# Sheet2.net
KiCad netlist of a schematic drawn in Altium Designer
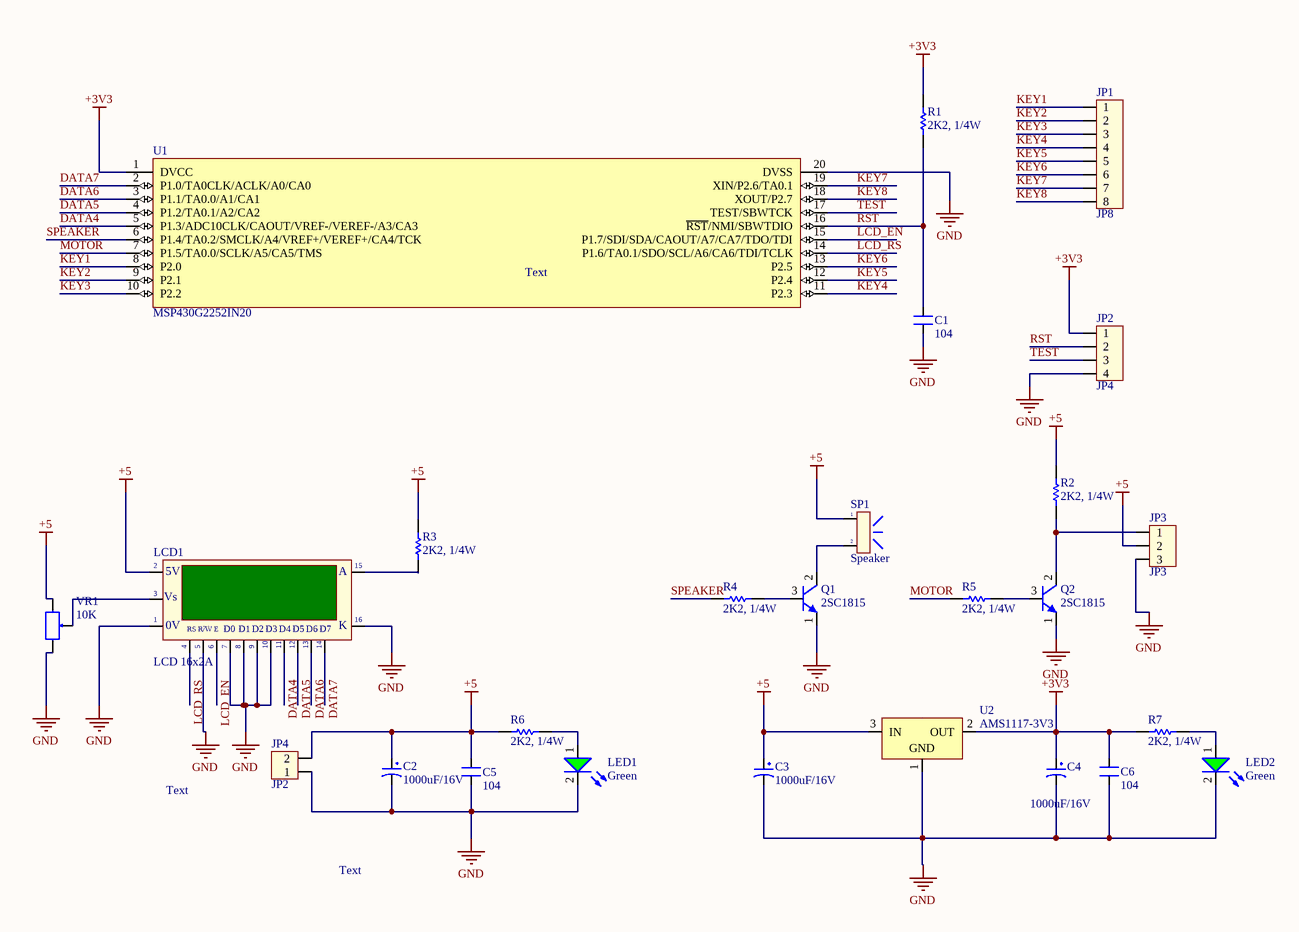
[diagram p0: Sheet2.SchDoc]

(export (version "E")
  (design (tool "Eeschema 10.0.6"))
  (components
    (comp (ref "C1")
      (value "104")
      (footprint "CN2")
      (description "Cap np 104 => 105pF")
      (libsource (lib "lpson") (part "CN2"))
    )
    (comp (ref "C2")
      (value "1000uF/16V")
      (footprint "CP1.5/3.4")
      (description "Cap 1000uF/16V - 220uF/50V")
      (libsource (lib "lpson") (part "CP4"))
    )
    (comp (ref "C3")
      (value "1000uF/16V")
      (footprint "CP1.5/3.4")
      (description "Cap 1000uF/16V - 220uF/50V")
      (libsource (lib "lpson") (part "CP4"))
    )
    (comp (ref "C4")
      (value "1000uF/16V")
      (footprint "CP1.5/3.4")
      (description "Cap 1000uF/16V - 220uF/50V")
      (libsource (lib "lpson") (part "CP4"))
    )
    (comp (ref "C5")
      (value "104")
      (footprint "CN2")
      (description "Cap np 104 => 105pF")
      (libsource (lib "lpson") (part "CN2"))
    )
    (comp (ref "C6")
      (value "104")
      (footprint "CN2")
      (description "Cap np 104 => 105pF")
      (libsource (lib "lpson") (part "CN2"))
    )
    (comp (ref "JP1")
      (value "JP8")
      (footprint "CON8")
      (description "Connector 8")
      (libsource (lib "lpson") (part "Con8"))
    )
    (comp (ref "JP2")
      (value "JP4")
      (footprint "CON4")
      (description "Connector 4")
      (libsource (lib "lpson") (part "Con4"))
    )
    (comp (ref "JP3")
      (value "JP3")
      (footprint "CON3")
      (description "Connector 3")
      (libsource (lib "lpson") (part "Con3"))
    )
    (comp (ref "JP4")
      (value "JP2")
      (footprint "CON2")
      (description "Connector 2")
      (libsource (lib "lpson") (part "Con2"))
    )
    (comp (ref "LCD1")
      (value "LCD 16x2A")
      (footprint "LCD16x2")
      (description "LCD dipslay 16 char, 2 line")
      (libsource (lib "lpson") (part "LCD16x2A"))
    )
    (comp (ref "LED1")
      (value "Green")
      (footprint "LED3G")
      (description "LED Green 3mm")
      (fields (field (name "Comment") "LED_G_3"))
      (libsource (lib "lpson") (part "LED_GREEN_3MM"))
    )
    (comp (ref "LED2")
      (value "Green")
      (footprint "LED3G")
      (description "LED Green 3mm")
      (fields (field (name "Comment") "LED_G_3"))
      (libsource (lib "lpson") (part "LED_GREEN_3MM"))
    )
    (comp (ref "Q1")
      (value "2SC1815")
      (footprint "2SC1815")
      (description "Trans NPN 50V 150mA TO-92")
      (libsource (lib "lpson") (part "2SC1815"))
    )
    (comp (ref "Q2")
      (value "2SC1815")
      (footprint "2SC1815")
      (description "Trans NPN 50V 150mA TO-92")
      (libsource (lib "lpson") (part "2SC1815"))
    )
    (comp (ref "R1")
      (value "2K2, 1/4W")
      (footprint "RES 1/4W CFR25")
      (description "RES CF AXIAL-0.3 5% 1/4W 2K2")
      (fields (field (name "Comment") "CF1/4W2K2J25"))
      (libsource (lib "lpson") (part "CF1/4W2K2J25"))
    )
    (comp (ref "R2")
      (value "2K2, 1/4W")
      (footprint "RES 1/4W CFR25")
      (description "RES CF AXIAL-0.3 5% 1/4W 2K2")
      (fields (field (name "Comment") "CF1/4W2K2J25"))
      (libsource (lib "lpson") (part "CF1/4W2K2J25"))
    )
    (comp (ref "R3")
      (value "2K2, 1/4W")
      (footprint "RES 1/4W CFR25")
      (description "RES CF AXIAL-0.3 5% 1/4W 2K2")
      (fields (field (name "Comment") "CF1/4W2K2J25"))
      (libsource (lib "lpson") (part "CF1/4W2K2J25"))
    )
    (comp (ref "R4")
      (value "2K2, 1/4W")
      (footprint "RES 1/4W CFR25")
      (description "RES CF AXIAL-0.3 5% 1/4W 2K2")
      (fields (field (name "Comment") "CF1/4W2K2J25"))
      (libsource (lib "lpson") (part "CF1/4W2K2J25"))
    )
    (comp (ref "R5")
      (value "2K2, 1/4W")
      (footprint "RES 1/4W CFR25")
      (description "RES CF AXIAL-0.3 5% 1/4W 2K2")
      (fields (field (name "Comment") "CF1/4W2K2J25"))
      (libsource (lib "lpson") (part "CF1/4W2K2J25"))
    )
    (comp (ref "R6")
      (value "2K2, 1/4W")
      (footprint "RES 1/4W CFR25")
      (description "RES CF AXIAL-0.3 5% 1/4W 2K2")
      (fields (field (name "Comment") "CF1/4W2K2J25"))
      (libsource (lib "lpson") (part "CF1/4W2K2J25"))
    )
    (comp (ref "R7")
      (value "2K2, 1/4W")
      (footprint "RES 1/4W CFR25")
      (description "RES CF AXIAL-0.3 5% 1/4W 2K2")
      (fields (field (name "Comment") "CF1/4W2K2J25"))
      (libsource (lib "lpson") (part "CF1/4W2K2J25"))
    )
    (comp (ref "SP1")
      (value "Speaker")
      (footprint "SPK")
      (description "Speaker Chip")
      (libsource (lib "lpson") (part "SPK"))
    )
    (comp (ref "U1")
      (value "MSP430G2252IN20")
      (footprint "MSP430G2552")
      (description "MCU 16bit 16KB 1.8-3.6V 16MHz DIP20")
      (libsource (lib "lpson") (part "MSP430G2252IN20"))
    )
    (comp (ref "U2")
      (value "AMS1117-3V3")
      (footprint "AMS1117-3.3V")
      (description "Linear Voltage Regulator 3.3V 1A 15V Max SOT-223")
      (libsource (lib "lpson") (part "AMS1117-3V3"))
    )
    (comp (ref "VR1")
      (value "10K")
      (footprint "VR1")
      (description "Var Resistor")
      (libsource (lib "lpson") (part "VR"))
    )
  )
  (nets
    (net (code "1") (name "+3V3") (class "Default")
      (node (ref "C4") (pin "1") (pinfunction "1_1") (pintype "passive"))
      (node (ref "C6") (pin "2") (pinfunction "2_2") (pintype "passive"))
      (node (ref "JP2") (pin "1") (pinfunction "1_1") (pintype "passive"))
      (node (ref "R1") (pin "2") (pinfunction "2_2") (pintype "passive"))
      (node (ref "R7") (pin "2") (pinfunction "2_2") (pintype "passive"))
      (node (ref "U1") (pin "1") (pinfunction "DVCC_1") (pintype "power_in"))
      (node (ref "U2") (pin "2") (pinfunction "OUT_2") (pintype "power_in"))
    )
    (net (code "2") (name "+5") (class "Default")
      (node (ref "C2") (pin "1") (pinfunction "1_1") (pintype "passive"))
      (node (ref "C3") (pin "1") (pinfunction "1_1") (pintype "passive"))
      (node (ref "C5") (pin "2") (pinfunction "2_2") (pintype "passive"))
      (node (ref "JP3") (pin "2") (pinfunction "2_2") (pintype "passive"))
      (node (ref "JP4") (pin "2") (pinfunction "2_2") (pintype "passive"))
      (node (ref "LCD1") (pin "2") (pinfunction "VDD_2") (pintype "passive"))
      (node (ref "R2") (pin "1") (pinfunction "1_1") (pintype "passive"))
      (node (ref "R3") (pin "2") (pinfunction "2_2") (pintype "passive"))
      (node (ref "R6") (pin "2") (pinfunction "2_2") (pintype "passive"))
      (node (ref "SP1") (pin "1") (pinfunction "1_1") (pintype "passive"))
      (node (ref "U2") (pin "3") (pinfunction "IN_3") (pintype "power_in"))
      (node (ref "VR1") (pin "1") (pinfunction "1_1") (pintype "passive"))
    )
    (net (code "3") (name "/DATA4") (class "Default")
      (node (ref "LCD1") (pin "11") (pinfunction "D4_11") (pintype "passive"))
      (node (ref "U1") (pin "5") (pinfunction "P1.3/ADC10CLK/CAOUT/VREF-/VEREF-/A3/CA3_5") (pintype "bidirectional"))
    )
    (net (code "4") (name "/DATA5") (class "Default")
      (node (ref "LCD1") (pin "12") (pinfunction "D5_12") (pintype "passive"))
      (node (ref "U1") (pin "4") (pinfunction "P1.2/TA0.1/A2/CA2_4") (pintype "bidirectional"))
    )
    (net (code "5") (name "/DATA6") (class "Default")
      (node (ref "LCD1") (pin "13") (pinfunction "D6_13") (pintype "passive"))
      (node (ref "U1") (pin "3") (pinfunction "P1.1/TA0.0/A1/CA1_3") (pintype "bidirectional"))
    )
    (net (code "6") (name "/DATA7") (class "Default")
      (node (ref "LCD1") (pin "14") (pinfunction "D7_14") (pintype "passive"))
      (node (ref "U1") (pin "2") (pinfunction "P1.0/TA0CLK/ACLK/A0/CA0_2") (pintype "bidirectional"))
    )
    (net (code "7") (name "/KEY1") (class "Default")
      (node (ref "JP1") (pin "1") (pinfunction "1_1") (pintype "passive"))
      (node (ref "U1") (pin "8") (pinfunction "P2.0_8") (pintype "bidirectional"))
    )
    (net (code "8") (name "/KEY2") (class "Default")
      (node (ref "JP1") (pin "2") (pinfunction "2_2") (pintype "passive"))
      (node (ref "U1") (pin "9") (pinfunction "P2.1_9") (pintype "bidirectional"))
    )
    (net (code "9") (name "/KEY3") (class "Default")
      (node (ref "JP1") (pin "3") (pinfunction "3_3") (pintype "passive"))
      (node (ref "U1") (pin "10") (pinfunction "P2.2_10") (pintype "bidirectional"))
    )
    (net (code "10") (name "/KEY4") (class "Default")
      (node (ref "JP1") (pin "4") (pinfunction "4_4") (pintype "passive"))
      (node (ref "U1") (pin "11") (pinfunction "P2.3_11") (pintype "bidirectional"))
    )
    (net (code "11") (name "/KEY5") (class "Default")
      (node (ref "JP1") (pin "5") (pinfunction "5_5") (pintype "passive"))
      (node (ref "U1") (pin "12") (pinfunction "P2.4_12") (pintype "bidirectional"))
    )
    (net (code "12") (name "/KEY6") (class "Default")
      (node (ref "JP1") (pin "6") (pinfunction "6_6") (pintype "passive"))
      (node (ref "U1") (pin "13") (pinfunction "P2.5_13") (pintype "bidirectional"))
    )
    (net (code "13") (name "/KEY7") (class "Default")
      (node (ref "JP1") (pin "7") (pinfunction "7_7") (pintype "passive"))
      (node (ref "U1") (pin "19") (pinfunction "XIN/P2.6/TA0.1_19") (pintype "bidirectional"))
    )
    (net (code "14") (name "/KEY8") (class "Default")
      (node (ref "JP1") (pin "8") (pinfunction "8_8") (pintype "passive"))
      (node (ref "U1") (pin "18") (pinfunction "XOUT/P2.7_18") (pintype "bidirectional"))
    )
    (net (code "15") (name "/LCD_EN") (class "Default")
      (node (ref "LCD1") (pin "6") (pinfunction "~{EN}_6") (pintype "passive"))
      (node (ref "U1") (pin "15") (pinfunction "P1.7/SDI/SDA/CAOUT/A7/CA7/TDO/TDI_15") (pintype "bidirectional"))
    )
    (net (code "16") (name "/LCD_RS") (class "Default")
      (node (ref "LCD1") (pin "4") (pinfunction "RS_4") (pintype "passive"))
      (node (ref "U1") (pin "14") (pinfunction "P1.6/TA0.1/SDO/SCL/A6/CA6/TDI/TCLK_14") (pintype "bidirectional"))
    )
    (net (code "17") (name "/MOTOR") (class "Default")
      (node (ref "R5") (pin "2") (pinfunction "2_2") (pintype "passive"))
      (node (ref "U1") (pin "7") (pinfunction "P1.5/TA0.0/SCLK/A5/CA5/TMS_7") (pintype "bidirectional"))
    )
    (net (code "18") (name "/RST") (class "Default")
      (node (ref "C1") (pin "2") (pinfunction "2_2") (pintype "passive"))
      (node (ref "JP2") (pin "2") (pinfunction "2_2") (pintype "passive"))
      (node (ref "R1") (pin "1") (pinfunction "1_1") (pintype "passive"))
      (node (ref "U1") (pin "16") (pinfunction "~{RST}/NMI/SBWTDIO_16") (pintype "bidirectional"))
    )
    (net (code "19") (name "/SPEAKER") (class "Default")
      (node (ref "R4") (pin "2") (pinfunction "2_2") (pintype "passive"))
      (node (ref "U1") (pin "6") (pinfunction "P1.4/TA0.2/SMCLK/A4/VREF+/VEREF+/CA4/TCK_6") (pintype "bidirectional"))
    )
    (net (code "20") (name "/TEST") (class "Default")
      (node (ref "JP2") (pin "3") (pinfunction "3_3") (pintype "passive"))
      (node (ref "U1") (pin "17") (pinfunction "TEST/SBWTCK_17") (pintype "bidirectional"))
    )
    (net (code "21") (name "GND") (class "Default")
      (node (ref "C1") (pin "1") (pinfunction "1_1") (pintype "passive"))
      (node (ref "C2") (pin "2") (pinfunction "2_2") (pintype "passive"))
      (node (ref "C3") (pin "2") (pinfunction "2_2") (pintype "passive"))
      (node (ref "C4") (pin "2") (pinfunction "2_2") (pintype "passive"))
      (node (ref "C5") (pin "1") (pinfunction "1_1") (pintype "passive"))
      (node (ref "C6") (pin "1") (pinfunction "1_1") (pintype "passive"))
      (node (ref "JP2") (pin "4") (pinfunction "4_4") (pintype "passive"))
      (node (ref "JP3") (pin "3") (pinfunction "3_3") (pintype "passive"))
      (node (ref "JP4") (pin "1") (pinfunction "1_1") (pintype "passive"))
      (node (ref "LCD1") (pin "1") (pinfunction "GND_1") (pintype "passive"))
      (node (ref "LCD1") (pin "10") (pinfunction "D3_10") (pintype "passive"))
      (node (ref "LCD1") (pin "16") (pinfunction "K_16") (pintype "passive"))
      (node (ref "LCD1") (pin "5") (pinfunction "R/~{W}_5") (pintype "passive"))
      (node (ref "LCD1") (pin "7") (pinfunction "D0_7") (pintype "passive"))
      (node (ref "LCD1") (pin "8") (pinfunction "D1_8") (pintype "passive"))
      (node (ref "LCD1") (pin "9") (pinfunction "D2_9") (pintype "passive"))
      (node (ref "LED1") (pin "2") (pinfunction "K_2") (pintype "passive"))
      (node (ref "LED2") (pin "2") (pinfunction "K_2") (pintype "passive"))
      (node (ref "Q1") (pin "1") (pinfunction "E_1") (pintype "passive"))
      (node (ref "Q2") (pin "1") (pinfunction "E_1") (pintype "passive"))
      (node (ref "U1") (pin "20") (pinfunction "DVSS_20") (pintype "power_in"))
      (node (ref "U2") (pin "1") (pinfunction "GND_1") (pintype "power_in"))
      (node (ref "VR1") (pin "3") (pinfunction "3_3") (pintype "passive"))
    )
    (net (code "22") (name "Net-(LCD1-A)") (class "Default")
      (node (ref "LCD1") (pin "15") (pinfunction "A_15") (pintype "passive"))
      (node (ref "R3") (pin "1") (pinfunction "1_1") (pintype "passive"))
    )
    (net (code "23") (name "Net-(LCD1-VEE)") (class "Default")
      (node (ref "LCD1") (pin "3") (pinfunction "VEE_3") (pintype "passive"))
      (node (ref "VR1") (pin "2") (pinfunction "2_2") (pintype "passive"))
    )
    (net (code "24") (name "Net-(LED1-A)") (class "Default")
      (node (ref "LED1") (pin "1") (pinfunction "A_1") (pintype "passive"))
      (node (ref "R6") (pin "1") (pinfunction "1_1") (pintype "passive"))
    )
    (net (code "25") (name "Net-(LED2-A)") (class "Default")
      (node (ref "LED2") (pin "1") (pinfunction "A_1") (pintype "passive"))
      (node (ref "R7") (pin "1") (pinfunction "1_1") (pintype "passive"))
    )
    (net (code "26") (name "Net-(Q1-B)") (class "Default")
      (node (ref "Q1") (pin "3") (pinfunction "B_3") (pintype "passive"))
      (node (ref "R4") (pin "1") (pinfunction "1_1") (pintype "passive"))
    )
    (net (code "27") (name "Net-(Q1-C)") (class "Default")
      (node (ref "Q1") (pin "2") (pinfunction "C_2") (pintype "passive"))
      (node (ref "SP1") (pin "2") (pinfunction "2_2") (pintype "passive"))
    )
    (net (code "28") (name "Net-(Q2-B)") (class "Default")
      (node (ref "Q2") (pin "3") (pinfunction "B_3") (pintype "passive"))
      (node (ref "R5") (pin "1") (pinfunction "1_1") (pintype "passive"))
    )
    (net (code "29") (name "Net-(Q2-C)") (class "Default")
      (node (ref "JP3") (pin "1") (pinfunction "1_1") (pintype "passive"))
      (node (ref "Q2") (pin "2") (pinfunction "C_2") (pintype "passive"))
      (node (ref "R2") (pin "2") (pinfunction "2_2") (pintype "passive"))
    )
    (net (code "30") (name "unconnected-(U2-OUT-Pad4)") (class "Default")
      (node (ref "U2") (pin "4") (pinfunction "OUT_4") (pintype "power_in"))
    )
  )
)
